# FOC_M.net
KiCad netlist of a schematic drawn in Altium Designer
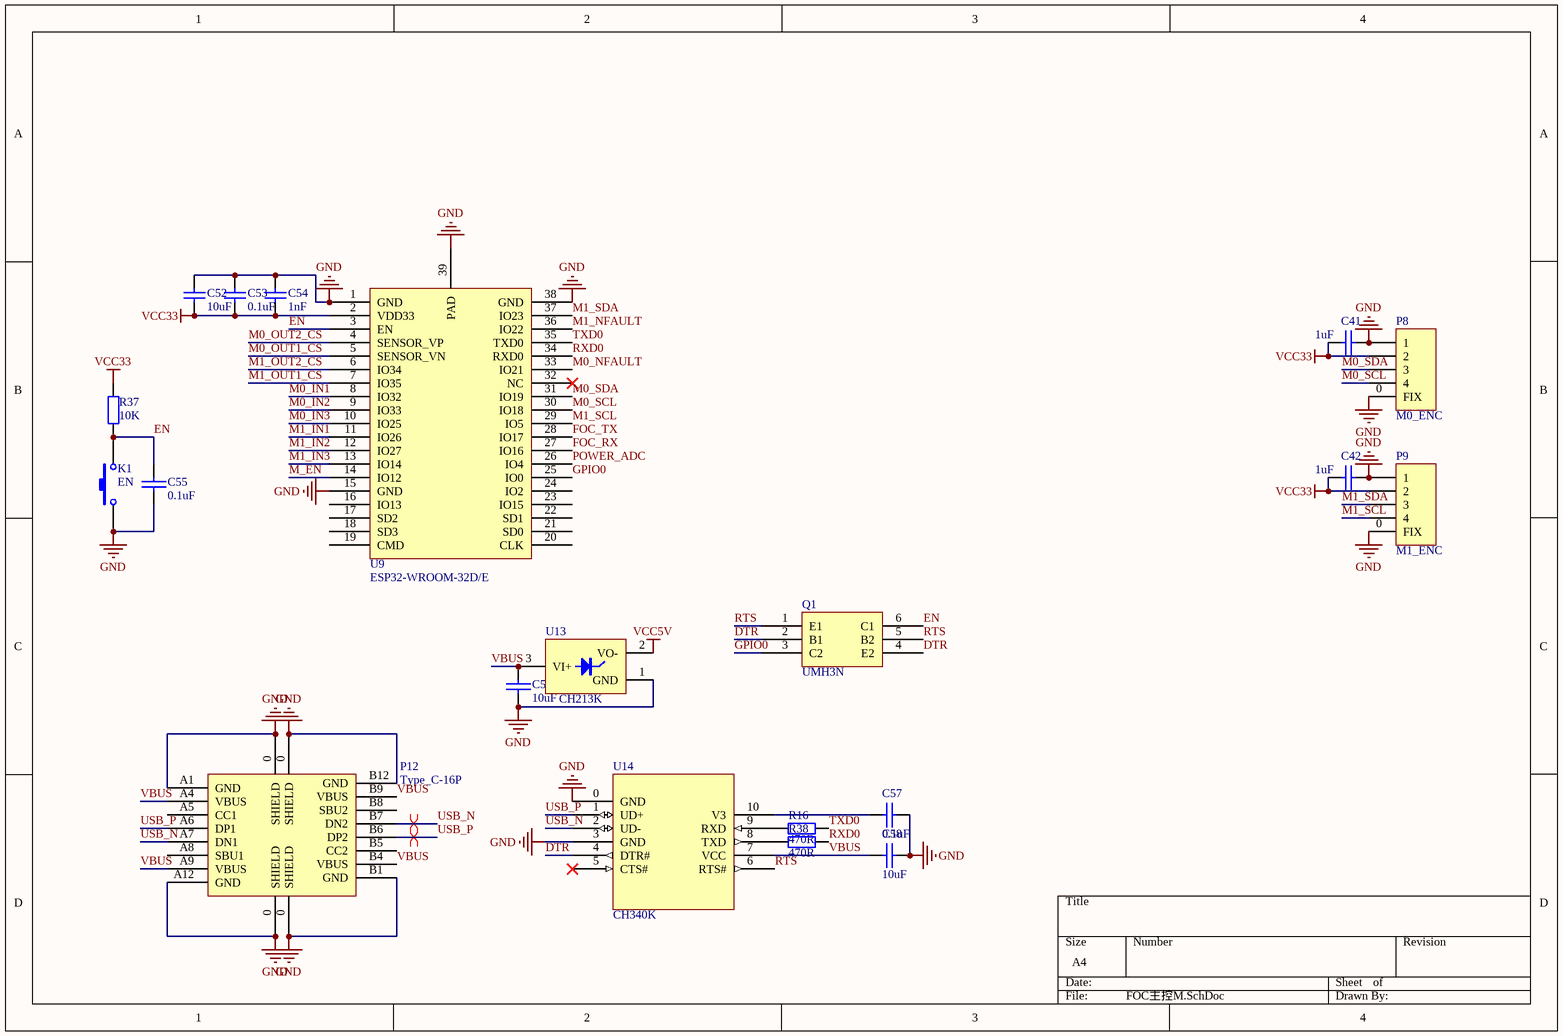
[diagram p0: FOC主控M.SchDoc]

(export (version "E")
  (design (tool "Eeschema 10.0.6"))
  (components
    (comp (ref "C41")
      (value "1uF")
      (footprint "C0805_M")
      (description "Capacitor")
      (libsource (lib "*") (part "CAP"))
    )
    (comp (ref "C42")
      (value "1uF")
      (footprint "C0805_M")
      (description "Capacitor")
      (libsource (lib "*") (part "CAP"))
    )
    (comp (ref "C52")
      (value "10uF")
      (footprint "C0805_M")
      (description "Capacitor")
      (fields (field (name "PUBLISHER") "Altium Limited"))
      (libsource (lib "Miscellaneous Devices") (part "Cap"))
    )
    (comp (ref "C53")
      (value "0.1uF")
      (footprint "C0805_M")
      (description "Capacitor")
      (fields (field (name "PUBLISHER") "Altium Limited"))
      (libsource (lib "Miscellaneous Devices") (part "Cap"))
    )
    (comp (ref "C54")
      (value "1nF")
      (footprint "C0805_M")
      (description "Capacitor")
      (fields (field (name "PUBLISHER") "Altium Limited"))
      (libsource (lib "Miscellaneous Devices") (part "Cap"))
    )
    (comp (ref "C55")
      (value "0.1uF")
      (footprint "C0805_M")
      (description "Capacitor")
      (libsource (lib "*") (part "CAP"))
    )
    (comp (ref "C56")
      (value "10uF")
      (footprint "C0805_M")
      (description "Capacitor")
      (libsource (lib "*") (part "CAP"))
    )
    (comp (ref "C57")
      (value "0.1uF")
      (footprint "C0805_M")
      (description "Capacitor")
      (libsource (lib "*") (part "CAP"))
    )
    (comp (ref "C58")
      (value "10uF")
      (footprint "C0805_M")
      (description "Capacitor")
      (libsource (lib "*") (part "CAP"))
    )
    (comp (ref "K1")
      (value "EN")
      (footprint "SW_SMT")
      (description "Switch")
      (fields (field (name "PUBLISHER") "Altium Limited"))
      (libsource (lib "Miscellaneous Devices") (part "SW-PB"))
    )
    (comp (ref "P8")
      (value "M0_ENC")
      (footprint "SH1.0-WT-4P")
      (fields (field (name "PUBLISHER") "Altium Limited"))
      (libsource (lib "Miscellaneous Connectors") (part "Header 5"))
    )
    (comp (ref "P9")
      (value "M1_ENC")
      (footprint "SH1.0-WT-4P")
      (fields (field (name "PUBLISHER") "Altium Limited"))
      (libsource (lib "Miscellaneous Connectors") (part "Header 5"))
    )
    (comp (ref "P12")
      (value "Type_C-16P")
      (footprint "USB-C-SMD_16P")
      (libsource (lib "XL6005") (part "Type_C-16P"))
    )
    (comp (ref "Q1")
      (value "UMH3N")
      (footprint "SOT363_M")
      (description "数字晶体管（带电阻）")
      (libsource (lib "XL6005") (part "D2NPN"))
    )
    (comp (ref "R16")
      (value "470R")
      (footprint "R0805_M")
      (description "Resistor")
      (fields (field (name "PUBLISHER") "Altium Limited"))
      (libsource (lib "Miscellaneous Devices") (part "Res2"))
    )
    (comp (ref "R37")
      (value "10K")
      (footprint "R0805_M")
      (description "Resistor")
      (fields (field (name "PUBLISHER") "Altium Limited"))
      (libsource (lib "") (part "Res2_1"))
    )
    (comp (ref "R38")
      (value "470R")
      (footprint "R0805_M")
      (description "Resistor")
      (fields (field (name "PUBLISHER") "Altium Limited"))
      (libsource (lib "Miscellaneous Devices") (part "Res2"))
    )
    (comp (ref "U9")
      (value "ESP32-WROOM-32D/E")
      (footprint "ESP32-WROOM-32D/E")
      (libsource (lib "XL6005") (part "ESP32-WROOM-32D/E"))
    )
    (comp (ref "U13")
      (value "CH213K")
      (footprint "SOT-23-3")
      (description "Ideal Diode 5V*1A")
      (libsource (lib "CHXXX") (part "CH213K"))
    )
    (comp (ref "U14")
      (value "CH340K")
      (footprint "ESSOP10")
      (description "USB to TTL Serial / UART for dual power")
      (libsource (lib "CHXXX") (part "CH340K"))
    )
  )
  (nets
    (net (code "1") (name "/DTR") (class "Default")
      (node (ref "Q1") (pin "2") (pinfunction "B1_2") (pintype "passive"))
      (node (ref "Q1") (pin "4") (pinfunction "E2_4") (pintype "passive"))
      (node (ref "U14") (pin "4") (pinfunction "DTR#_4") (pintype "output"))
    )
    (net (code "2") (name "/EN") (class "Default")
      (node (ref "C55") (pin "2") (pinfunction "2_2") (pintype "passive"))
      (node (ref "K1") (pin "2") (pinfunction "2_2") (pintype "passive"))
      (node (ref "Q1") (pin "6") (pinfunction "C1_6") (pintype "passive"))
      (node (ref "R37") (pin "2") (pinfunction "2_2") (pintype "passive"))
      (node (ref "U9") (pin "3") (pinfunction "EN_3") (pintype "passive"))
    )
    (net (code "3") (name "/FOC_RX") (class "Default")
      (node (ref "U9") (pin "27") (pinfunction "IO16_27") (pintype "passive"))
    )
    (net (code "4") (name "/FOC_TX") (class "Default")
      (node (ref "U9") (pin "28") (pinfunction "IO17_28") (pintype "passive"))
    )
    (net (code "5") (name "/GPIO0") (class "Default")
      (node (ref "Q1") (pin "3") (pinfunction "C2_3") (pintype "passive"))
      (node (ref "U9") (pin "25") (pinfunction "IO0_25") (pintype "passive"))
    )
    (net (code "6") (name "/M0_IN1") (class "Default")
      (node (ref "U9") (pin "8") (pinfunction "IO32_8") (pintype "passive"))
    )
    (net (code "7") (name "/M0_IN2") (class "Default")
      (node (ref "U9") (pin "9") (pinfunction "IO33_9") (pintype "passive"))
    )
    (net (code "8") (name "/M0_IN3") (class "Default")
      (node (ref "U9") (pin "10") (pinfunction "IO25_10") (pintype "passive"))
    )
    (net (code "9") (name "/M0_NFAULT") (class "Default")
      (node (ref "U9") (pin "33") (pinfunction "IO21_33") (pintype "passive"))
    )
    (net (code "10") (name "/M0_OUT1_CS") (class "Default")
      (node (ref "U9") (pin "5") (pinfunction "SENSOR_VN_5") (pintype "passive"))
    )
    (net (code "11") (name "/M0_OUT2_CS") (class "Default")
      (node (ref "U9") (pin "4") (pinfunction "SENSOR_VP_4") (pintype "passive"))
    )
    (net (code "12") (name "/M0_SCL") (class "Default")
      (node (ref "P8") (pin "4") (pinfunction "4_4") (pintype "passive"))
      (node (ref "U9") (pin "30") (pinfunction "IO18_30") (pintype "passive"))
    )
    (net (code "13") (name "/M0_SDA") (class "Default")
      (node (ref "P8") (pin "3") (pinfunction "3_3") (pintype "passive"))
      (node (ref "U9") (pin "31") (pinfunction "IO19_31") (pintype "passive"))
    )
    (net (code "14") (name "/M1_IN1") (class "Default")
      (node (ref "U9") (pin "11") (pinfunction "IO26_11") (pintype "passive"))
    )
    (net (code "15") (name "/M1_IN2") (class "Default")
      (node (ref "U9") (pin "12") (pinfunction "IO27_12") (pintype "passive"))
    )
    (net (code "16") (name "/M1_IN3") (class "Default")
      (node (ref "U9") (pin "13") (pinfunction "IO14_13") (pintype "passive"))
    )
    (net (code "17") (name "/M1_NFAULT") (class "Default")
      (node (ref "U9") (pin "36") (pinfunction "IO22_36") (pintype "passive"))
    )
    (net (code "18") (name "/M1_OUT1_CS") (class "Default")
      (node (ref "U9") (pin "7") (pinfunction "IO35_7") (pintype "passive"))
    )
    (net (code "19") (name "/M1_OUT2_CS") (class "Default")
      (node (ref "U9") (pin "6") (pinfunction "IO34_6") (pintype "passive"))
    )
    (net (code "20") (name "/M1_SCL") (class "Default")
      (node (ref "P9") (pin "4") (pinfunction "4_4") (pintype "passive"))
      (node (ref "U9") (pin "29") (pinfunction "IO5_29") (pintype "passive"))
    )
    (net (code "21") (name "/M1_SDA") (class "Default")
      (node (ref "P9") (pin "3") (pinfunction "3_3") (pintype "passive"))
      (node (ref "U9") (pin "37") (pinfunction "IO23_37") (pintype "passive"))
    )
    (net (code "22") (name "/M_EN") (class "Default")
      (node (ref "U9") (pin "14") (pinfunction "IO12_14") (pintype "passive"))
    )
    (net (code "23") (name "/POWER_ADC") (class "Default")
      (node (ref "U9") (pin "26") (pinfunction "IO4_26") (pintype "passive"))
    )
    (net (code "24") (name "/RTS") (class "Default")
      (node (ref "Q1") (pin "1") (pinfunction "E1_1") (pintype "passive"))
      (node (ref "Q1") (pin "5") (pinfunction "B2_5") (pintype "passive"))
      (node (ref "U14") (pin "6") (pinfunction "RTS#_6") (pintype "output"))
    )
    (net (code "25") (name "/RXD0") (class "Default")
      (node (ref "R38") (pin "2") (pinfunction "2_2") (pintype "passive"))
      (node (ref "U9") (pin "34") (pinfunction "RXD0_34") (pintype "passive"))
    )
    (net (code "26") (name "/TXD0") (class "Default")
      (node (ref "R16") (pin "2") (pinfunction "2_2") (pintype "passive"))
      (node (ref "U9") (pin "35") (pinfunction "TXD0_35") (pintype "passive"))
    )
    (net (code "27") (name "/USB_N") (class "Default")
      (node (ref "P12") (pin "A7") (pinfunction "DN1_A7") (pintype "passive"))
      (node (ref "P12") (pin "B7") (pinfunction "DN2_B7") (pintype "passive"))
      (node (ref "U14") (pin "2") (pinfunction "UD-_2") (pintype "bidirectional"))
    )
    (net (code "28") (name "/USB_P") (class "Default")
      (node (ref "P12") (pin "A6") (pinfunction "DP1_A6") (pintype "passive"))
      (node (ref "P12") (pin "B6") (pinfunction "DP2_B6") (pintype "passive"))
      (node (ref "U14") (pin "1") (pinfunction "UD+_1") (pintype "bidirectional"))
    )
    (net (code "29") (name "/VBUS") (class "Default")
      (node (ref "C56") (pin "2") (pinfunction "2_2") (pintype "passive"))
      (node (ref "C58") (pin "2") (pinfunction "2_2") (pintype "passive"))
      (node (ref "P12") (pin "A4") (pinfunction "VBUS_A4") (pintype "passive"))
      (node (ref "P12") (pin "A9") (pinfunction "VBUS_A9") (pintype "passive"))
      (node (ref "P12") (pin "B4") (pinfunction "VBUS_B4") (pintype "passive"))
      (node (ref "P12") (pin "B9") (pinfunction "VBUS_B9") (pintype "passive"))
      (node (ref "U13") (pin "3") (pinfunction "VI+_3") (pintype "power_in"))
      (node (ref "U14") (pin "7") (pinfunction "VCC_7") (pintype "power_in"))
    )
    (net (code "30") (name "GND") (class "Default")
      (node (ref "C41") (pin "2") (pinfunction "2_2") (pintype "passive"))
      (node (ref "C42") (pin "2") (pinfunction "2_2") (pintype "passive"))
      (node (ref "C52") (pin "2") (pinfunction "2_2") (pintype "passive"))
      (node (ref "C53") (pin "2") (pinfunction "2_2") (pintype "passive"))
      (node (ref "C54") (pin "2") (pinfunction "2_2") (pintype "passive"))
      (node (ref "C55") (pin "1") (pinfunction "1_1") (pintype "passive"))
      (node (ref "C56") (pin "1") (pinfunction "1_1") (pintype "passive"))
      (node (ref "C57") (pin "1") (pinfunction "1_1") (pintype "passive"))
      (node (ref "C58") (pin "1") (pinfunction "1_1") (pintype "passive"))
      (node (ref "K1") (pin "1") (pinfunction "1_1") (pintype "passive"))
      (node (ref "P12") (pin "0") (pinfunction "SHIELD_0") (pintype "passive"))
      (node (ref "P12") (pin "A1") (pinfunction "GND_A1") (pintype "passive"))
      (node (ref "P12") (pin "A12") (pinfunction "GND_A12") (pintype "passive"))
      (node (ref "P12") (pin "B1") (pinfunction "GND_B1") (pintype "passive"))
      (node (ref "P12") (pin "B12") (pinfunction "GND_B12") (pintype "passive"))
      (node (ref "P8") (pin "0") (pinfunction "FIX_0") (pintype "passive"))
      (node (ref "P8") (pin "1") (pinfunction "1_1") (pintype "passive"))
      (node (ref "P9") (pin "0") (pinfunction "FIX_0") (pintype "passive"))
      (node (ref "P9") (pin "1") (pinfunction "1_1") (pintype "passive"))
      (node (ref "U13") (pin "1") (pinfunction "GND_1") (pintype "power_in"))
      (node (ref "U14") (pin "0") (pinfunction "GND_0") (pintype "power_in"))
      (node (ref "U14") (pin "3") (pinfunction "GND_3") (pintype "power_in"))
      (node (ref "U9") (pin "1") (pinfunction "GND_1") (pintype "passive"))
      (node (ref "U9") (pin "15") (pinfunction "GND_15") (pintype "passive"))
      (node (ref "U9") (pin "38") (pinfunction "GND_38") (pintype "passive"))
      (node (ref "U9") (pin "39") (pinfunction "PAD_39") (pintype "passive"))
    )
    (net (code "31") (name "Net-(U14-RXD)") (class "Default")
      (node (ref "R16") (pin "1") (pinfunction "1_1") (pintype "passive"))
      (node (ref "U14") (pin "9") (pinfunction "RXD_9") (pintype "input"))
    )
    (net (code "32") (name "Net-(U14-TXD)") (class "Default")
      (node (ref "R38") (pin "1") (pinfunction "1_1") (pintype "passive"))
      (node (ref "U14") (pin "8") (pinfunction "TXD_8") (pintype "output"))
    )
    (net (code "33") (name "Net-(U14-V3)") (class "Default")
      (node (ref "C57") (pin "2") (pinfunction "2_2") (pintype "passive"))
      (node (ref "U14") (pin "10") (pinfunction "V3_10") (pintype "power_in"))
    )
    (net (code "34") (name "VCC5V") (class "Default")
      (node (ref "U13") (pin "2") (pinfunction "VO-_2") (pintype "power_in"))
    )
    (net (code "35") (name "VCC33") (class "Default")
      (node (ref "C41") (pin "1") (pinfunction "1_1") (pintype "passive"))
      (node (ref "C42") (pin "1") (pinfunction "1_1") (pintype "passive"))
      (node (ref "C52") (pin "1") (pinfunction "1_1") (pintype "passive"))
      (node (ref "C53") (pin "1") (pinfunction "1_1") (pintype "passive"))
      (node (ref "C54") (pin "1") (pinfunction "1_1") (pintype "passive"))
      (node (ref "P8") (pin "2") (pinfunction "2_2") (pintype "passive"))
      (node (ref "P9") (pin "2") (pinfunction "2_2") (pintype "passive"))
      (node (ref "R37") (pin "1") (pinfunction "1_1") (pintype "passive"))
      (node (ref "U9") (pin "2") (pinfunction "VDD33_2") (pintype "passive"))
    )
    (net (code "36") (name "unconnected-(P12-CC1-PadA5)") (class "Default")
      (node (ref "P12") (pin "A5") (pinfunction "CC1_A5") (pintype "passive"))
    )
    (net (code "37") (name "unconnected-(P12-CC2-PadB5)") (class "Default")
      (node (ref "P12") (pin "B5") (pinfunction "CC2_B5") (pintype "passive"))
    )
    (net (code "38") (name "unconnected-(P12-SBU1-PadA8)") (class "Default")
      (node (ref "P12") (pin "A8") (pinfunction "SBU1_A8") (pintype "passive"))
    )
    (net (code "39") (name "unconnected-(P12-SBU2-PadB8)") (class "Default")
      (node (ref "P12") (pin "B8") (pinfunction "SBU2_B8") (pintype "passive"))
    )
    (net (code "40") (name "unconnected-(U9-CLK-Pad20)") (class "Default")
      (node (ref "U9") (pin "20") (pinfunction "CLK_20") (pintype "passive"))
    )
    (net (code "41") (name "unconnected-(U9-CMD-Pad19)") (class "Default")
      (node (ref "U9") (pin "19") (pinfunction "CMD_19") (pintype "passive"))
    )
    (net (code "42") (name "unconnected-(U9-IO2-Pad24)") (class "Default")
      (node (ref "U9") (pin "24") (pinfunction "IO2_24") (pintype "passive"))
    )
    (net (code "43") (name "unconnected-(U9-IO13-Pad16)") (class "Default")
      (node (ref "U9") (pin "16") (pinfunction "IO13_16") (pintype "passive"))
    )
    (net (code "44") (name "unconnected-(U9-IO15-Pad23)") (class "Default")
      (node (ref "U9") (pin "23") (pinfunction "IO15_23") (pintype "passive"))
    )
    (net (code "45") (name "unconnected-(U9-NC-Pad32)") (class "Default")
      (node (ref "U9") (pin "32") (pinfunction "NC_32") (pintype "passive+no_connect"))
    )
    (net (code "46") (name "unconnected-(U9-SD0-Pad21)") (class "Default")
      (node (ref "U9") (pin "21") (pinfunction "SD0_21") (pintype "passive"))
    )
    (net (code "47") (name "unconnected-(U9-SD1-Pad22)") (class "Default")
      (node (ref "U9") (pin "22") (pinfunction "SD1_22") (pintype "passive"))
    )
    (net (code "48") (name "unconnected-(U9-SD2-Pad17)") (class "Default")
      (node (ref "U9") (pin "17") (pinfunction "SD2_17") (pintype "passive"))
    )
    (net (code "49") (name "unconnected-(U9-SD3-Pad18)") (class "Default")
      (node (ref "U9") (pin "18") (pinfunction "SD3_18") (pintype "passive"))
    )
    (net (code "50") (name "unconnected-(U14-CTS#-Pad5)") (class "Default")
      (node (ref "U14") (pin "5") (pinfunction "CTS#_5") (pintype "input+no_connect"))
    )
  )
)
